# Gate_Driver.net
KiCad netlist of a schematic drawn in Altium Designer
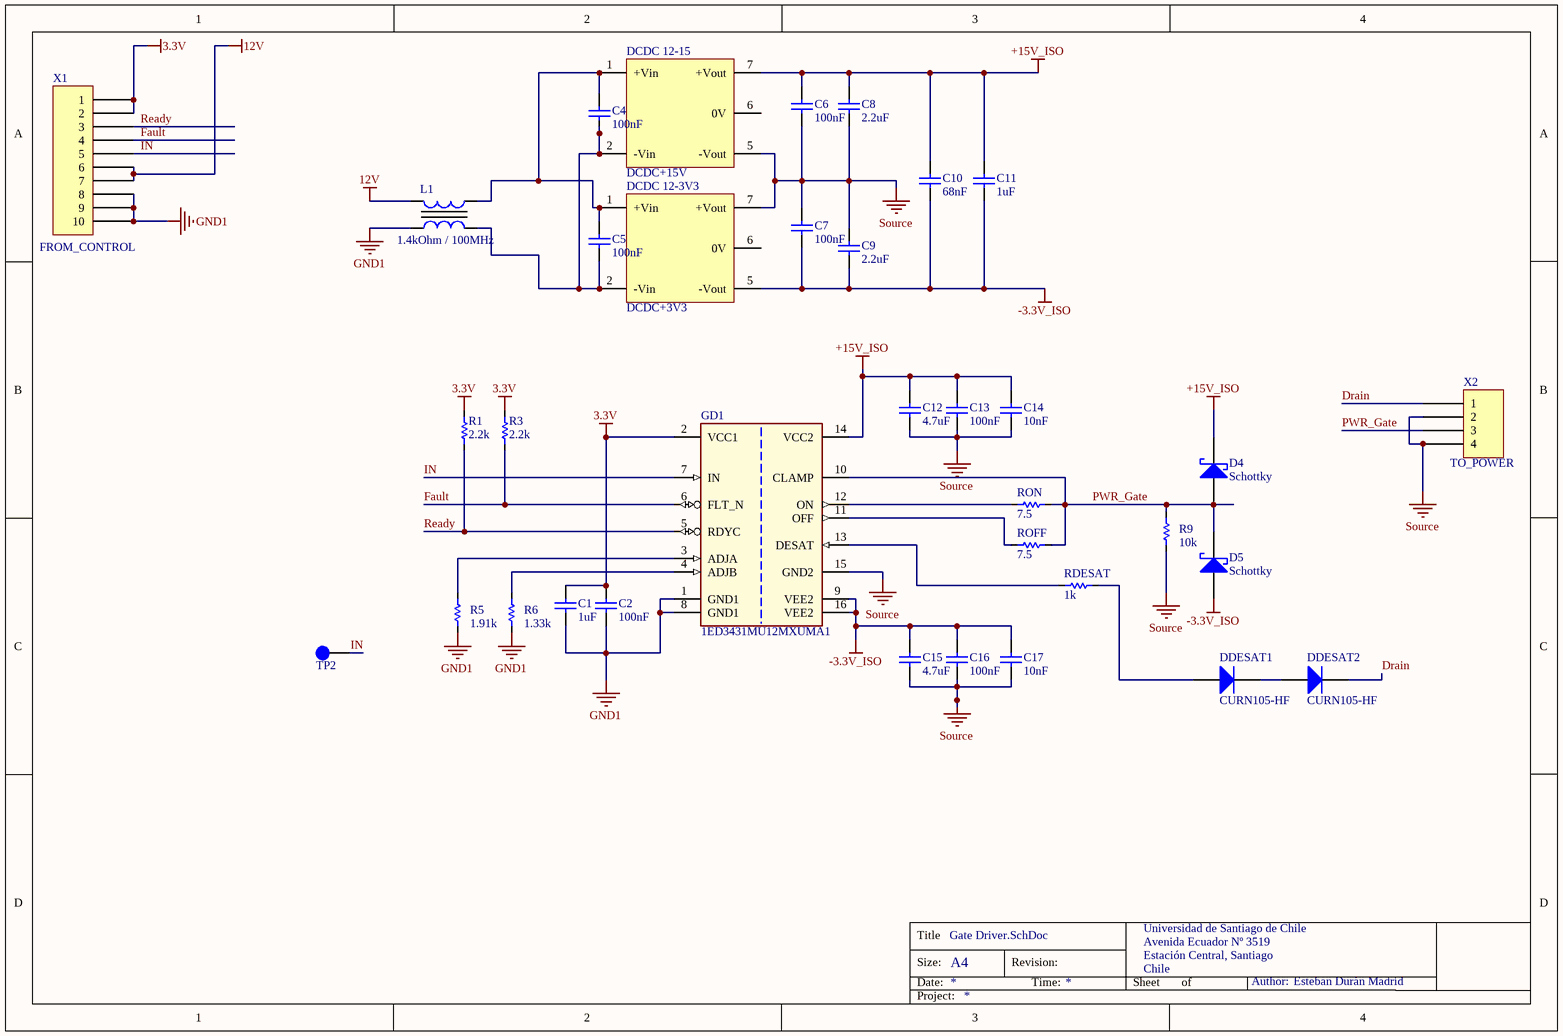
[diagram p0: Gate Driver.SchDoc]

(export (version "E")
  (design (tool "Eeschema 10.0.6"))
  (components
    (comp (ref "C1")
      (value "1uF")
      (footprint "CAP_0805")
      (description "1µF ±10% 50V Ceramic Capacitor X7R 0805 (2012 Metric)")
      (fields
        (field (name "MF") "KEMET")
        (field (name "MPN") "C0805C105K5RACAUTO")
        (field (name "CREATED") "2020_06_15_DAarancibia")
      )
      (libsource (lib "H-Bridge_Lib") (part "Cap_0805"))
    )
    (comp (ref "C2")
      (value "100nF")
      (footprint "CAP_0603")
      (description "0.1µF ±10% 50V Ceramic Capacitor X7R 0603 (2012 Metric)")
      (fields (field (name "MF") "KEMET") (field (name "MPN") "C0805C104K5RACTU"))
      (libsource (lib "H-Bridge_Lib") (part "Cap_0805"))
    )
    (comp (ref "C4")
      (value "100nF")
      (footprint "CAP_0603")
      (description "0.1µF ±10% 50V Ceramic Capacitor X7R 0603 (2012 Metric)")
      (fields (field (name "MF") "KEMET") (field (name "MPN") "C0805C104K5RACTU"))
      (libsource (lib "H-Bridge_Lib") (part "Cap_0805"))
    )
    (comp (ref "C5")
      (value "100nF")
      (footprint "CAP_0603")
      (description "0.1µF ±10% 50V Ceramic Capacitor X7R 0603 (2012 Metric)")
      (fields (field (name "MF") "KEMET") (field (name "MPN") "C0805C104K5RACTU"))
      (libsource (lib "H-Bridge_Lib") (part "Cap_0805"))
    )
    (comp (ref "C6")
      (value "100nF")
      (footprint "CAP_0603")
      (description "0.1µF ±10% 50V Ceramic Capacitor X7R 0603 (2012 Metric)")
      (fields (field (name "MF") "KEMET") (field (name "MPN") "C0805C104K5RACTU"))
      (libsource (lib "H-Bridge_Lib") (part "Cap_0805"))
    )
    (comp (ref "C7")
      (value "100nF")
      (footprint "CAP_0603")
      (description "0.1µF ±10% 50V Ceramic Capacitor X7R 0603 (2012 Metric)")
      (fields (field (name "MF") "KEMET") (field (name "MPN") "C0805C104K5RACTU"))
      (libsource (lib "H-Bridge_Lib") (part "Cap_0805"))
    )
    (comp (ref "C8")
      (value "2.2uF")
      (footprint "CAP_0805")
      (description "2.2µF ±10% 50V Ceramic Capacitor X7R 0805 (2012 Metric)")
      (fields (field (name "MF") "KEMET"))
      (libsource (lib "H-Bridge_Lib") (part "Cap_0805"))
    )
    (comp (ref "C9")
      (value "2.2uF")
      (footprint "CAP_0805")
      (description "2.2µF ±10% 50V Ceramic Capacitor X7R 0805 (2012 Metric)")
      (fields (field (name "MF") "KEMET"))
      (libsource (lib "H-Bridge_Lib") (part "Cap_0805"))
    )
    (comp (ref "C10")
      (value "68nF")
      (footprint "CAP_0603")
      (description "0.1µF ±10% 50V Ceramic Capacitor X7R 0603 (2012 Metric)")
      (fields (field (name "MF") "KEMET") (field (name "MPN") "C0805C104K5RACTU"))
      (libsource (lib "H-Bridge_Lib") (part "Cap_0805"))
    )
    (comp (ref "C11")
      (value "1uF")
      (footprint "CAP_0805")
      (description "1µF ±10% 50V Ceramic Capacitor X7R 0805 (2012 Metric)")
      (fields
        (field (name "MF") "KEMET")
        (field (name "MPN") "C0805C105K5RACAUTO")
        (field (name "CREATED") "2020_06_15_DAarancibia")
      )
      (libsource (lib "H-Bridge_Lib") (part "Cap_0805"))
    )
    (comp (ref "C12")
      (value "4.7uF")
      (footprint "CAP_0805")
      (description "4.7µF ±10% 35V Ceramic Capacitor X7R 0805 (2012 Metric)")
      (fields (field (name "MF") "murata"))
      (libsource (lib "H-Bridge_Lib") (part "Cap_0805"))
    )
    (comp (ref "C13")
      (value "100nF")
      (footprint "CAP_0603")
      (description "0.1µF ±10% 50V Ceramic Capacitor X7R 0603 (2012 Metric)")
      (fields (field (name "MF") "KEMET") (field (name "MPN") "C0805C104K5RACTU"))
      (libsource (lib "H-Bridge_Lib") (part "Cap_0805"))
    )
    (comp (ref "C14")
      (value "10nF")
      (footprint "CAP_0603")
      (description "0.01µF ±10% 50V Ceramic Capacitor X7R 0603 (2012 Metric)")
      (fields (field (name "MF") "KEMET") (field (name "MPN") "C0805C104K5RACTU"))
      (libsource (lib "H-Bridge_Lib") (part "Cap_0805"))
    )
    (comp (ref "C15")
      (value "4.7uF")
      (footprint "CAP_0805")
      (description "4.7µF ±10% 35V Ceramic Capacitor X7R 0805 (2012 Metric)")
      (fields (field (name "MF") "murata"))
      (libsource (lib "H-Bridge_Lib") (part "Cap_0805"))
    )
    (comp (ref "C16")
      (value "100nF")
      (footprint "CAP_0603")
      (description "0.1µF ±10% 50V Ceramic Capacitor X7R 0603 (2012 Metric)")
      (fields (field (name "MF") "KEMET") (field (name "MPN") "C0805C104K5RACTU"))
      (libsource (lib "H-Bridge_Lib") (part "Cap_0805"))
    )
    (comp (ref "C17")
      (value "10nF")
      (footprint "CAP_0603")
      (description "0.01µF ±10% 50V Ceramic Capacitor X7R 0603 (2012 Metric)")
      (fields (field (name "MF") "KEMET") (field (name "MPN") "C0805C104K5RACTU"))
      (libsource (lib "H-Bridge_Lib") (part "Cap_0805"))
    )
    (comp (ref "D4")
      (value "Schottky")
      (footprint "SOD-123")
      (description "Diode Schottky 30 V 1A Surface Mount PG-SOD323-2")
      (fields
        (field (name "MF") "Infineon Technologies")
        (field (name "MPN") "BAS3010B03WE6327HTSA1")
        (field (name "CREATED") "2021_05_16_EDuran")
      )
      (libsource (lib "Gate-Driver_Lib") (part "Diode_Schottky_30V/1A"))
    )
    (comp (ref "D5")
      (value "Schottky")
      (footprint "SOD-123")
      (description "Diode Schottky 30 V 1A Surface Mount PG-SOD323-2")
      (fields
        (field (name "MF") "Infineon Technologies")
        (field (name "MPN") "BAS3010B03WE6327HTSA1")
        (field (name "CREATED") "2021_05_16_EDuran")
      )
      (libsource (lib "Gate-Driver_Lib") (part "Diode_Schottky_30V/1A"))
    )
    (comp (ref "DCDC 12-3V3")
      (value "DCDC+3V3")
      (footprint "DC-DC-GEN")
      (description "ISOLATED DC-DC CONVERTER 12V INPUT, 3.3V OUTPUT")
      (fields (field (name "MF") "TRACO") (field (name "MPN") "TMV 1203SHI"))
      (libsource (lib "Isolated gate driver module - Lib") (part "DC_DC_123V3"))
    )
    (comp (ref "DCDC 12-15")
      (value "DCDC+15V")
      (footprint "DC-DC-GEN")
      (description "ISOLATED DC-DC CONVERTER 12V INPUT, 15V OUTPUT")
      (fields (field (name "MF") "TRACO") (field (name "MPN") "TBA 1-1213HI"))
      (libsource (lib "Isolated gate driver module - Lib") (part "DC_DC_1215"))
    )
    (comp (ref "DDESAT1")
      (value "CURN105-HF")
      (footprint "DIODE_1206")
      (description "Diode Standard 1000V 1A Surface Mount 1206")
      (libsource (lib "Isolated gate driver module - Lib") (part "Diode_2"))
    )
    (comp (ref "DDESAT2")
      (value "CURN105-HF")
      (footprint "DIODE_1206")
      (description "Diode Standard 1000V 1A Surface Mount 1206")
      (libsource (lib "Isolated gate driver module - Lib") (part "Diode_2"))
    )
    (comp (ref "GD1")
      (value "1ED3431MU12MXUMA1")
      (footprint "SOP65P1030X265-16N-1")
      (description "3A Gate Driver Capacitive Coupling - Channel PG-DSO-16-28")
      (fields (field (name "MF") "Infineon Technologies") (field (name "CREATED") "2021_05_15_EDuran"))
      (libsource (lib "Gate-Driver_Lib") (part "1ED3431MU12M"))
    )
    (comp (ref "L1")
      (value "1.4kOhm / 100MHz")
      (footprint "CHOKE_CM_4.7x4.5mm")
      (description "2 Line Common Mode Choke Surface Mount 1.4 kOhms @ 100MHz 1.7A DCR 80mOhm")
      (fields
        (field (name "MF") "TDK Corporation")
        (field (name "MPN") "ACM4520-142-2P-T000")
        (field (name "CREATED") "2020_07_28_DAarancibia")
      )
      (libsource (lib "H-Bridge_Lib") (part "Choke_CM_ACM4520"))
    )
    (comp (ref "R1")
      (value "2.2k")
      (footprint "RES_0603")
      (description "2.2 kOhms ±5% 0.1W, 1/10W Chip Resistor 0603 (1608 Metric) Moisture Resistant Thick Film")
      (fields (field (name "MF") "Bourns Inc.") (field (name "CREATED") "2020_06_15_DAarancibia"))
      (libsource (lib "Gate-Driver_Lib") (part "Res_0603"))
    )
    (comp (ref "R3")
      (value "2.2k")
      (footprint "RES_0603")
      (description "2.2 kOhms ±5% 0.1W, 1/10W Chip Resistor 0603 (1608 Metric) Moisture Resistant Thick Film")
      (fields (field (name "MF") "Bourns Inc.") (field (name "CREATED") "2020_06_15_DAarancibia"))
      (libsource (lib "Gate-Driver_Lib") (part "Res_0603"))
    )
    (comp (ref "R5")
      (value "1.91k")
      (footprint "RES_0603")
      (description "1.91 kOhms ±1% 0.1W, 1/10W Chip Resistor 0603 (1608 Metric) Moisture Resistant Thick Film")
      (fields (field (name "MF") "Yageo") (field (name "CREATED") "2020_06_15_DAarancibia"))
      (libsource (lib "Gate-Driver_Lib") (part "Res_0603"))
    )
    (comp (ref "R6")
      (value "1.33k")
      (footprint "RES_0603")
      (description "1.33 kOhms ±1% 0.1W, 1/10W Chip Resistor 0603 (1608 Metric)")
      (fields (field (name "MF") "YAGEO"))
      (libsource (lib "Gate-Driver_Lib") (part "Res_0603"))
    )
    (comp (ref "R9")
      (value "10k")
      (footprint "RES_0603")
      (description "10 kOhms ±5% 0.1W, 1/10W Chip Resistor 0603 (1608 Metric) Moisture Resistant Thick Film")
      (fields (field (name "MF") "Yageo") (field (name "CREATED") "2020_06_15_DAarancibia"))
      (libsource (lib "H-Bridge_Lib") (part "Res_0603"))
    )
    (comp (ref "RDESAT")
      (value "1k")
      (footprint "RES_0603")
      (fields (field (name "MF") "Yageo") (field (name "CREATED") "2020_06_15_DAarancibia"))
      (libsource (lib "H-Bridge_Lib") (part "Res_0603"))
    )
    (comp (ref "ROFF")
      (value "7.5")
      (footprint "RES_MMB_0207")
      (description "7.5 Ohms ±1% 1W Chip Resistor MELF, 0207 Anti-Sulfur, Automotive AEC-Q200 Thin Film")
      (fields (field (name "MF") "Vishay Beyschlag"))
      (libsource (lib "H-Bridge_Lib") (part "Res_MELF_0207"))
    )
    (comp (ref "RON")
      (value "7.5")
      (footprint "RES_MMB_0207")
      (description "7.5 Ohms ±1% 1W Chip Resistor MELF, 0207 Anti-Sulfur, Automotive AEC-Q200 Thin Film")
      (fields (field (name "MF") "Vishay Beyschlag"))
      (libsource (lib "H-Bridge_Lib") (part "Res_MELF_0207"))
    )
    (comp (ref "TP2")
      (value "Gate")
      (footprint "TP_1mm")
      (description "Testpoint 1mm")
      (fields (field (name "CREATED") "2018_06_25_AGeiger"))
      (libsource (lib "H-Bridge_Lib") (part "TP_1mm"))
    )
    (comp (ref "X1")
      (value "FROM_CONTROL")
      (footprint "TMM-110-01-G-S")
      (description "Connector Header Through Hole 10 position 0.079\" (2.00mm)")
      (fields
        (field (name "MF") "Samtec Inc.")
        (field (name "MPN") "TMM-110-01-G-S")
        (field (name "CREATED") "2021_05_24_EDuran")
      )
      (libsource (lib "Gate-Driver_Lib") (part "Con_Header_Male_6"))
    )
    (comp (ref "X2")
      (value "TO_POWER")
      (footprint "TMM-104-01-G-S")
      (description "Connector Header Through Hole 4 position 0.079\" (2.00mm)")
      (fields
        (field (name "MF") "Samtec Inc.")
        (field (name "MPN") "TMM-104-01-G-S")
        (field (name "CREATED") "2021_05_24_EDuran")
      )
      (libsource (lib "Gate-Driver_Lib") (part "Con_Header_Male_5"))
    )
  )
  (nets
    (net (code "1") (name "+15V_ISO") (class "Default")
      (node (ref "C10") (pin "1") (pinfunction "1_1") (pintype "passive"))
      (node (ref "C11") (pin "1") (pinfunction "1_1") (pintype "passive"))
      (node (ref "C12") (pin "1") (pinfunction "1_1") (pintype "passive"))
      (node (ref "C13") (pin "1") (pinfunction "1_1") (pintype "passive"))
      (node (ref "C14") (pin "1") (pinfunction "1_1") (pintype "passive"))
      (node (ref "C6") (pin "1") (pinfunction "1_1") (pintype "passive"))
      (node (ref "C8") (pin "1") (pinfunction "1_1") (pintype "passive"))
      (node (ref "D4") (pin "K") (pinfunction "K_K") (pintype "passive"))
      (node (ref "DCDC 12-15") (pin "7") (pinfunction "+Vout_7") (pintype "passive"))
      (node (ref "GD1") (pin "14") (pinfunction "VCC2_14") (pintype "power_in"))
    )
    (net (code "2") (name "-3.3V_ISO") (class "Default")
      (node (ref "C10") (pin "2") (pinfunction "2_2") (pintype "passive"))
      (node (ref "C11") (pin "2") (pinfunction "2_2") (pintype "passive"))
      (node (ref "C15") (pin "1") (pinfunction "1_1") (pintype "passive"))
      (node (ref "C16") (pin "1") (pinfunction "1_1") (pintype "passive"))
      (node (ref "C17") (pin "1") (pinfunction "1_1") (pintype "passive"))
      (node (ref "C7") (pin "2") (pinfunction "2_2") (pintype "passive"))
      (node (ref "C9") (pin "2") (pinfunction "2_2") (pintype "passive"))
      (node (ref "D5") (pin "A") (pinfunction "A_A") (pintype "passive"))
      (node (ref "DCDC 12-3V3") (pin "5") (pinfunction "-Vout_5") (pintype "passive"))
      (node (ref "GD1") (pin "16") (pinfunction "VEE2_16") (pintype "power_in"))
      (node (ref "GD1") (pin "9") (pinfunction "VEE2_9") (pintype "power_in"))
    )
    (net (code "3") (name "/Drain") (class "Default")
      (node (ref "DDESAT2") (pin "K") (pinfunction "K_K") (pintype "passive"))
      (node (ref "X2") (pin "1") (pinfunction "1_1") (pintype "passive"))
    )
    (net (code "4") (name "/Fault") (class "Default")
      (node (ref "GD1") (pin "6") (pinfunction "FLT_N_6") (pintype "bidirectional"))
      (node (ref "R3") (pin "1") (pinfunction "1_1") (pintype "passive"))
      (node (ref "X1") (pin "4") (pinfunction "4_4") (pintype "passive"))
    )
    (net (code "5") (name "/IN") (class "Default")
      (node (ref "GD1") (pin "7") (pinfunction "IN_7") (pintype "input"))
      (node (ref "TP2") (pin "1") (pintype "passive"))
      (node (ref "X1") (pin "5") (pinfunction "5_5") (pintype "passive"))
    )
    (net (code "6") (name "/PWR_Gate") (class "Default")
      (node (ref "D4") (pin "A") (pinfunction "A_A") (pintype "passive"))
      (node (ref "D5") (pin "K") (pinfunction "K_K") (pintype "passive"))
      (node (ref "GD1") (pin "10") (pinfunction "CLAMP_10") (pintype "passive"))
      (node (ref "R9") (pin "2") (pinfunction "2_2") (pintype "passive"))
      (node (ref "ROFF") (pin "1") (pinfunction "1_1") (pintype "passive"))
      (node (ref "RON") (pin "1") (pinfunction "1_1") (pintype "passive"))
      (node (ref "X2") (pin "3") (pinfunction "3_3") (pintype "passive"))
    )
    (net (code "7") (name "/Ready") (class "Default")
      (node (ref "GD1") (pin "5") (pinfunction "RDYC_5") (pintype "bidirectional"))
      (node (ref "R1") (pin "1") (pinfunction "1_1") (pintype "passive"))
      (node (ref "X1") (pin "3") (pinfunction "3_3") (pintype "passive"))
    )
    (net (code "8") (name "3.3V") (class "Default")
      (node (ref "C1") (pin "1") (pinfunction "1_1") (pintype "passive"))
      (node (ref "C2") (pin "1") (pinfunction "1_1") (pintype "passive"))
      (node (ref "GD1") (pin "2") (pinfunction "VCC1_2") (pintype "power_in"))
      (node (ref "R1") (pin "2") (pinfunction "2_2") (pintype "passive"))
      (node (ref "R3") (pin "2") (pinfunction "2_2") (pintype "passive"))
      (node (ref "X1") (pin "1") (pinfunction "1_1") (pintype "passive"))
      (node (ref "X1") (pin "2") (pinfunction "2_2") (pintype "passive"))
    )
    (net (code "9") (name "12V") (class "Default")
      (node (ref "L1") (pin "3") (pinfunction "3_3") (pintype "passive"))
      (node (ref "X1") (pin "6") (pinfunction "6_6") (pintype "passive"))
      (node (ref "X1") (pin "7") (pinfunction "7_7") (pintype "passive"))
    )
    (net (code "10") (name "GND1") (class "Default")
      (node (ref "C1") (pin "2") (pinfunction "2_2") (pintype "passive"))
      (node (ref "C2") (pin "2") (pinfunction "2_2") (pintype "passive"))
      (node (ref "GD1") (pin "1") (pinfunction "GND1_1") (pintype "power_in"))
      (node (ref "GD1") (pin "8") (pinfunction "GND1_8") (pintype "power_in"))
      (node (ref "L1") (pin "4") (pinfunction "4_4") (pintype "passive"))
      (node (ref "R5") (pin "1") (pinfunction "1_1") (pintype "passive"))
      (node (ref "R6") (pin "1") (pinfunction "1_1") (pintype "passive"))
      (node (ref "X1") (pin "10") (pinfunction "10_10") (pintype "passive"))
      (node (ref "X1") (pin "8") (pinfunction "8_8") (pintype "passive"))
      (node (ref "X1") (pin "9") (pinfunction "9_9") (pintype "passive"))
    )
    (net (code "11") (name "Net-(DCDC 12-15-+Vin)") (class "Default")
      (node (ref "C4") (pin "1") (pinfunction "1_1") (pintype "passive"))
      (node (ref "C5") (pin "1") (pinfunction "1_1") (pintype "passive"))
      (node (ref "DCDC 12-15") (pin "1") (pinfunction "+Vin_1") (pintype "passive"))
      (node (ref "DCDC 12-3V3") (pin "1") (pinfunction "+Vin_1") (pintype "passive"))
      (node (ref "L1") (pin "2") (pinfunction "2_2") (pintype "passive"))
    )
    (net (code "12") (name "Net-(DCDC 12-15--Vin)") (class "Default")
      (node (ref "C4") (pin "2") (pinfunction "2_2") (pintype "passive"))
      (node (ref "C5") (pin "2") (pinfunction "2_2") (pintype "passive"))
      (node (ref "DCDC 12-15") (pin "2") (pinfunction "-Vin_2") (pintype "passive"))
      (node (ref "DCDC 12-3V3") (pin "2") (pinfunction "-Vin_2") (pintype "passive"))
      (node (ref "L1") (pin "1") (pinfunction "1_1") (pintype "passive"))
    )
    (net (code "13") (name "Net-(DDESAT1-PadA)") (class "Default")
      (node (ref "DDESAT1") (pin "A") (pinfunction "A_A") (pintype "passive"))
      (node (ref "RDESAT") (pin "2") (pinfunction "2_2") (pintype "passive"))
    )
    (net (code "14") (name "Net-(DDESAT1-PadK)") (class "Default")
      (node (ref "DDESAT1") (pin "K") (pinfunction "K_K") (pintype "passive"))
      (node (ref "DDESAT2") (pin "A") (pinfunction "A_A") (pintype "passive"))
    )
    (net (code "15") (name "Net-(GD1-ADJA)") (class "Default")
      (node (ref "GD1") (pin "3") (pinfunction "ADJA_3") (pintype "input"))
      (node (ref "R5") (pin "2") (pinfunction "2_2") (pintype "passive"))
    )
    (net (code "16") (name "Net-(GD1-ADJB)") (class "Default")
      (node (ref "GD1") (pin "4") (pinfunction "ADJB_4") (pintype "input"))
      (node (ref "R6") (pin "2") (pinfunction "2_2") (pintype "passive"))
    )
    (net (code "17") (name "Net-(GD1-DESAT)") (class "Default")
      (node (ref "GD1") (pin "13") (pinfunction "DESAT_13") (pintype "input"))
      (node (ref "RDESAT") (pin "1") (pinfunction "1_1") (pintype "passive"))
    )
    (net (code "18") (name "Net-(GD1-OFF)") (class "Default")
      (node (ref "GD1") (pin "11") (pinfunction "OFF_11") (pintype "output"))
      (node (ref "ROFF") (pin "2") (pinfunction "2_2") (pintype "passive"))
    )
    (net (code "19") (name "Net-(GD1-ON)") (class "Default")
      (node (ref "GD1") (pin "12") (pinfunction "ON_12") (pintype "output"))
      (node (ref "RON") (pin "2") (pinfunction "2_2") (pintype "passive"))
    )
    (net (code "20") (name "Source") (class "Default")
      (node (ref "C12") (pin "2") (pinfunction "2_2") (pintype "passive"))
      (node (ref "C13") (pin "2") (pinfunction "2_2") (pintype "passive"))
      (node (ref "C14") (pin "2") (pinfunction "2_2") (pintype "passive"))
      (node (ref "C15") (pin "2") (pinfunction "2_2") (pintype "passive"))
      (node (ref "C16") (pin "2") (pinfunction "2_2") (pintype "passive"))
      (node (ref "C17") (pin "2") (pinfunction "2_2") (pintype "passive"))
      (node (ref "C6") (pin "2") (pinfunction "2_2") (pintype "passive"))
      (node (ref "C7") (pin "1") (pinfunction "1_1") (pintype "passive"))
      (node (ref "C8") (pin "2") (pinfunction "2_2") (pintype "passive"))
      (node (ref "C9") (pin "1") (pinfunction "1_1") (pintype "passive"))
      (node (ref "DCDC 12-15") (pin "5") (pinfunction "-Vout_5") (pintype "passive"))
      (node (ref "DCDC 12-3V3") (pin "7") (pinfunction "+Vout_7") (pintype "passive"))
      (node (ref "GD1") (pin "15") (pinfunction "GND2_15") (pintype "power_in"))
      (node (ref "R9") (pin "1") (pinfunction "1_1") (pintype "passive"))
      (node (ref "X2") (pin "2") (pinfunction "2_2") (pintype "passive"))
      (node (ref "X2") (pin "4") (pinfunction "4_4") (pintype "passive"))
    )
    (net (code "21") (name "unconnected-(DCDC 12-3V3-0V-Pad6)") (class "Default")
      (node (ref "DCDC 12-3V3") (pin "6") (pinfunction "0V_6") (pintype "passive"))
    )
    (net (code "22") (name "unconnected-(DCDC 12-15-0V-Pad6)") (class "Default")
      (node (ref "DCDC 12-15") (pin "6") (pinfunction "0V_6") (pintype "passive"))
    )
  )
)
